# Power.net
KiCad netlist of a schematic drawn in Altium Designer
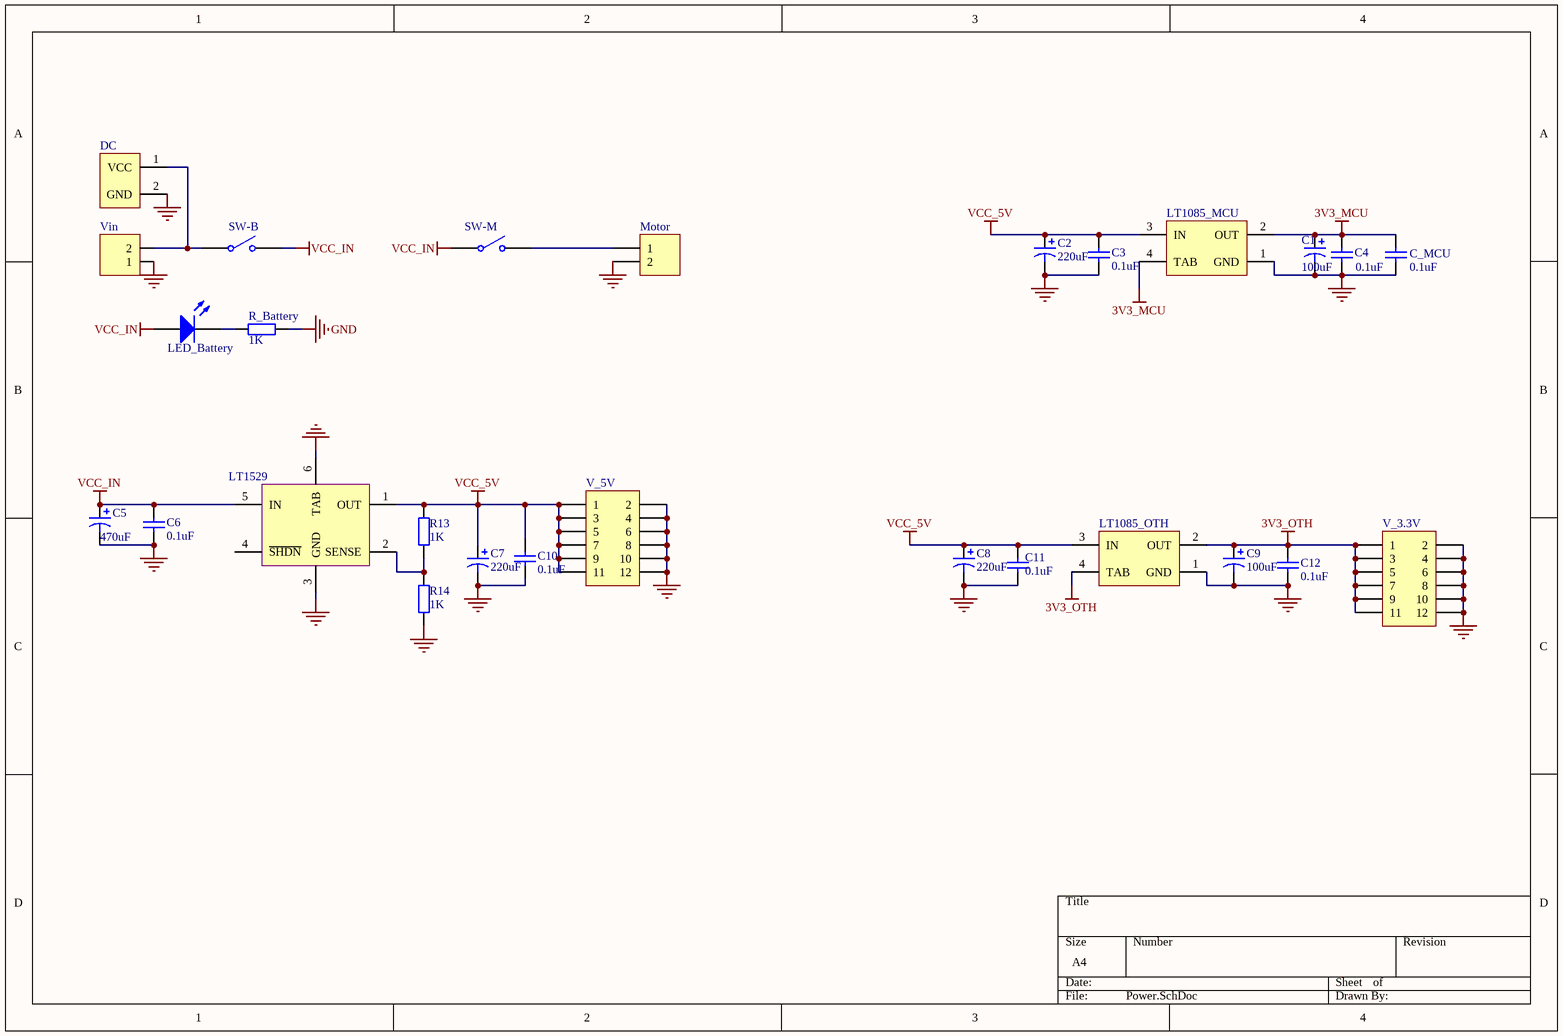
[diagram p0: Power.SchDoc]

(export (version "E")
  (design (tool "Eeschema 10.0.6"))
  (components
    (comp (ref "C1")
      (value "100uF")
      (footprint "100uf-25V")
      (description "Polarized Capacitor (Radial)")
      (fields (field (name "Comment") "100uf") (field (name "PUBLISHER") "Altium Limited"))
      (libsource (lib "Miscellaneous Devices") (part "Cap Pol1"))
    )
    (comp (ref "C2")
      (value "220uF")
      (footprint "220UF-25V")
      (description "Polarized Capacitor (Radial)")
      (fields (field (name "Comment") "220uf") (field (name "PUBLISHER") "Altium Limited"))
      (libsource (lib "Miscellaneous Devices") (part "Cap Pol1"))
    )
    (comp (ref "C3")
      (value "0.1uF")
      (footprint "0805-S")
      (description "Capacitor")
      (fields (field (name "Comment") "0.1uf") (field (name "PUBLISHER") "Altium Limited"))
      (libsource (lib "Miscellaneous Devices") (part "Cap"))
    )
    (comp (ref "C4")
      (value "0.1uF")
      (footprint "0805-S")
      (description "Capacitor")
      (fields (field (name "Comment") "0.1uf") (field (name "PUBLISHER") "Altium Limited"))
      (libsource (lib "Miscellaneous Devices") (part "Cap"))
    )
    (comp (ref "C5")
      (value "470uF")
      (footprint "220UF-25V")
      (description "Polarized Capacitor (Radial)")
      (fields (field (name "Comment") "470uf") (field (name "PUBLISHER") "Altium Limited"))
      (libsource (lib "Miscellaneous Devices") (part "Cap Pol1"))
    )
    (comp (ref "C6")
      (value "0.1uF")
      (footprint "0805-S")
      (description "Capacitor")
      (fields (field (name "PUBLISHER") "Altium Limited"))
      (libsource (lib "lichao_Library") (part "Cap_1"))
    )
    (comp (ref "C7")
      (value "220uF")
      (footprint "220UF-25V")
      (description "Polarized Capacitor (Radial)")
      (fields (field (name "Comment") "220uf") (field (name "PUBLISHER") "Altium Limited"))
      (libsource (lib "Miscellaneous Devices") (part "Cap Pol1"))
    )
    (comp (ref "C8")
      (value "220uF")
      (footprint "220UF-25V")
      (description "Polarized Capacitor (Radial)")
      (fields (field (name "Comment") "220uf") (field (name "PUBLISHER") "Altium Limited"))
      (libsource (lib "Miscellaneous Devices") (part "Cap Pol1"))
    )
    (comp (ref "C9")
      (value "100uF")
      (footprint "100uf-25V")
      (description "Polarized Capacitor (Radial)")
      (fields (field (name "Comment") "100uf") (field (name "PUBLISHER") "Altium Limited"))
      (libsource (lib "Miscellaneous Devices") (part "Cap Pol1"))
    )
    (comp (ref "C10")
      (value "0.1uF")
      (footprint "0805-S")
      (description "Capacitor")
      (fields (field (name "PUBLISHER") "Altium Limited"))
      (libsource (lib "lichao_Library") (part "Cap_1"))
    )
    (comp (ref "C11")
      (value "0.1uF")
      (footprint "0805-S")
      (description "Capacitor")
      (fields (field (name "Comment") "0.1uf") (field (name "PUBLISHER") "Altium Limited"))
      (libsource (lib "Miscellaneous Devices") (part "Cap"))
    )
    (comp (ref "C12")
      (value "0.1uF")
      (footprint "0805-S")
      (description "Capacitor")
      (fields (field (name "Comment") "0.1uf") (field (name "PUBLISHER") "Altium Limited"))
      (libsource (lib "Miscellaneous Devices") (part "Cap"))
    )
    (comp (ref "C_MCU")
      (value "0.1uF")
      (footprint "0805-S")
      (description "Capacitor")
      (fields (field (name "Comment") "0.1uf") (field (name "PUBLISHER") "Altium Limited"))
      (libsource (lib "Miscellaneous Devices") (part "Cap"))
    )
    (comp (ref "DC") (value "DC0005") (footprint "DC") (libsource (lib "lichao_Library") (part "DC0005")))
    (comp (ref "LED_Battery")
      (value "LED")
      (footprint "0805-S")
      (description "Typical INFRARED GaAs LED")
      (fields (field (name "PUBLISHER") "Altium Limited"))
      (libsource (lib "Miscellaneous Devices") (part "LED0"))
    )
    (comp (ref "LT1085_MCU")
      (value "LT1085-3.3")
      (footprint "TS3B_N")
      (libsource (lib "lichao_Library") (part "LT1085-3.3"))
    )
    (comp (ref "LT1085_OTH")
      (value "LT1085-3.3")
      (footprint "TS3B_N")
      (libsource (lib "lichao_Library") (part "LT1085-3.3"))
    )
    (comp (ref "LT1529")
      (value "LT1529")
      (footprint "TS5B")
      (libsource (lib "lichao_Library") (part "LT1529"))
    )
    (comp (ref "Motor")
      (value "Header 2")
      (footprint "Head2_small")
      (description "Header, 2-Pin")
      (fields (field (name "PUBLISHER") "Altium Limited"))
      (libsource (lib "") (part "Header 2_1"))
    )
    (comp (ref "R13")
      (value "1K")
      (footprint "0805-S")
      (description "Resistor")
      (fields (field (name "PUBLISHER") "Altium Limited"))
      (libsource (lib "lichao_Library") (part "Res2_3"))
    )
    (comp (ref "R14")
      (value "1K")
      (footprint "0805-S")
      (description "Resistor")
      (fields (field (name "PUBLISHER") "Altium Limited"))
      (libsource (lib "lichao_Library") (part "Res2_3"))
    )
    (comp (ref "R_Battery")
      (value "1K")
      (footprint "0805-S")
      (description "Resistor")
      (fields (field (name "PUBLISHER") "Altium Limited"))
      (libsource (lib "Miscellaneous Devices") (part "Res2"))
    )
    (comp (ref "SW-B")
      (value "SW-TOGGLE")
      (footprint "SW-TOGGLE")
      (description "Single-Pole, Single-Throw Switch")
      (fields (field (name "PUBLISHER") "Altium Limited"))
      (libsource (lib "lichao_Library") (part "SW-TOGGLE"))
    )
    (comp (ref "SW-M")
      (value "SW-TOGGLE")
      (footprint "SW-TOGGLE")
      (description "Single-Pole, Single-Throw Switch")
      (fields (field (name "PUBLISHER") "Altium Limited"))
      (libsource (lib "lichao_Library") (part "SW-TOGGLE"))
    )
    (comp (ref "Vin")
      (value "Header 2")
      (footprint "Head2_small")
      (description "Header, 2-Pin")
      (fields (field (name "PUBLISHER") "Altium Limited"))
      (libsource (lib "Miscellaneous Connectors") (part "Header 2"))
    )
    (comp (ref "V_3.3V")
      (value "Header 6X2")
      (footprint "HDR2X6")
      (description "Header, 6-Pin, Dual row")
      (fields (field (name "PUBLISHER") "Altium Limited"))
      (libsource (lib "Miscellaneous Connectors") (part "Header 6X2"))
    )
    (comp (ref "V_5V")
      (value "Header 6X2")
      (footprint "HDR2X6")
      (description "Header, 6-Pin, Dual row")
      (fields (field (name "PUBLISHER") "Altium Limited"))
      (libsource (lib "Miscellaneous Connectors") (part "Header 6X2"))
    )
  )
  (nets
    (net (code "1") (name "3V3_MCU") (class "Default")
      (node (ref "C1") (pin "1") (pinfunction "1_1") (pintype "passive"))
      (node (ref "C4") (pin "2") (pinfunction "2_2") (pintype "passive"))
      (node (ref "C_MCU") (pin "2") (pinfunction "2_2") (pintype "passive"))
      (node (ref "LT1085_MCU") (pin "2") (pinfunction "OUT_2") (pintype "power_in"))
      (node (ref "LT1085_MCU") (pin "4") (pinfunction "TAB_4") (pintype "power_in"))
    )
    (net (code "2") (name "3V3_OTH") (class "Default")
      (node (ref "C12") (pin "2") (pinfunction "2_2") (pintype "passive"))
      (node (ref "C9") (pin "1") (pinfunction "1_1") (pintype "passive"))
      (node (ref "LT1085_OTH") (pin "2") (pinfunction "OUT_2") (pintype "power_in"))
      (node (ref "LT1085_OTH") (pin "4") (pinfunction "TAB_4") (pintype "power_in"))
      (node (ref "V_3.3V") (pin "1") (pinfunction "1_1") (pintype "passive"))
      (node (ref "V_3.3V") (pin "11") (pinfunction "11_11") (pintype "passive"))
      (node (ref "V_3.3V") (pin "3") (pinfunction "3_3") (pintype "passive"))
      (node (ref "V_3.3V") (pin "5") (pinfunction "5_5") (pintype "passive"))
      (node (ref "V_3.3V") (pin "7") (pinfunction "7_7") (pintype "passive"))
      (node (ref "V_3.3V") (pin "9") (pinfunction "9_9") (pintype "passive"))
    )
    (net (code "3") (name "GND") (class "Default")
      (node (ref "C1") (pin "2") (pinfunction "2_2") (pintype "passive"))
      (node (ref "C10") (pin "1") (pinfunction "1_1") (pintype "passive"))
      (node (ref "C11") (pin "1") (pinfunction "1_1") (pintype "passive"))
      (node (ref "C12") (pin "1") (pinfunction "1_1") (pintype "passive"))
      (node (ref "C2") (pin "2") (pinfunction "2_2") (pintype "passive"))
      (node (ref "C3") (pin "1") (pinfunction "1_1") (pintype "passive"))
      (node (ref "C4") (pin "1") (pinfunction "1_1") (pintype "passive"))
      (node (ref "C5") (pin "2") (pinfunction "2_2") (pintype "passive"))
      (node (ref "C6") (pin "1") (pinfunction "1_1") (pintype "passive"))
      (node (ref "C7") (pin "2") (pinfunction "2_2") (pintype "passive"))
      (node (ref "C8") (pin "2") (pinfunction "2_2") (pintype "passive"))
      (node (ref "C9") (pin "2") (pinfunction "2_2") (pintype "passive"))
      (node (ref "C_MCU") (pin "1") (pinfunction "1_1") (pintype "passive"))
      (node (ref "DC") (pin "2") (pinfunction "GND_2") (pintype "open_collector"))
      (node (ref "LT1085_MCU") (pin "1") (pinfunction "GND_1") (pintype "power_in"))
      (node (ref "LT1085_OTH") (pin "1") (pinfunction "GND_1") (pintype "power_in"))
      (node (ref "LT1529") (pin "3") (pinfunction "GND_3") (pintype "passive"))
      (node (ref "LT1529") (pin "6") (pinfunction "TAB_6") (pintype "open_collector"))
      (node (ref "Motor") (pin "2") (pinfunction "2_2") (pintype "passive"))
      (node (ref "R14") (pin "1") (pinfunction "1_1") (pintype "passive"))
      (node (ref "R_Battery") (pin "1") (pinfunction "1_1") (pintype "passive"))
      (node (ref "V_3.3V") (pin "10") (pinfunction "10_10") (pintype "passive"))
      (node (ref "V_3.3V") (pin "12") (pinfunction "12_12") (pintype "passive"))
      (node (ref "V_3.3V") (pin "2") (pinfunction "2_2") (pintype "passive"))
      (node (ref "V_3.3V") (pin "4") (pinfunction "4_4") (pintype "passive"))
      (node (ref "V_3.3V") (pin "6") (pinfunction "6_6") (pintype "passive"))
      (node (ref "V_3.3V") (pin "8") (pinfunction "8_8") (pintype "passive"))
      (node (ref "V_5V") (pin "10") (pinfunction "10_10") (pintype "passive"))
      (node (ref "V_5V") (pin "12") (pinfunction "12_12") (pintype "passive"))
      (node (ref "V_5V") (pin "2") (pinfunction "2_2") (pintype "passive"))
      (node (ref "V_5V") (pin "4") (pinfunction "4_4") (pintype "passive"))
      (node (ref "V_5V") (pin "6") (pinfunction "6_6") (pintype "passive"))
      (node (ref "V_5V") (pin "8") (pinfunction "8_8") (pintype "passive"))
      (node (ref "Vin") (pin "1") (pinfunction "1_1") (pintype "passive"))
    )
    (net (code "4") (name "Net-(DC-VCC)") (class "Default")
      (node (ref "DC") (pin "1") (pinfunction "VCC_1") (pintype "open_collector"))
      (node (ref "SW-B") (pin "1") (pinfunction "COMMON_1") (pintype "passive"))
      (node (ref "Vin") (pin "2") (pinfunction "2_2") (pintype "passive"))
    )
    (net (code "5") (name "Net-(LED_Battery-K)") (class "Default")
      (node (ref "LED_Battery") (pin "2") (pinfunction "K_2") (pintype "passive"))
      (node (ref "R_Battery") (pin "2") (pinfunction "2_2") (pintype "passive"))
    )
    (net (code "6") (name "Net-(LT1529-SENSE)") (class "Default")
      (node (ref "LT1529") (pin "2") (pinfunction "SENSE_2") (pintype "passive"))
      (node (ref "R13") (pin "1") (pinfunction "1_1") (pintype "passive"))
      (node (ref "R14") (pin "2") (pinfunction "2_2") (pintype "passive"))
    )
    (net (code "7") (name "Net-(SW-M-NO)") (class "Default")
      (node (ref "Motor") (pin "1") (pinfunction "1_1") (pintype "passive"))
      (node (ref "SW-M") (pin "2") (pinfunction "NO_2") (pintype "passive"))
    )
    (net (code "8") (name "VCC_5V") (class "Default")
      (node (ref "C10") (pin "2") (pinfunction "2_2") (pintype "passive"))
      (node (ref "C11") (pin "2") (pinfunction "2_2") (pintype "passive"))
      (node (ref "C2") (pin "1") (pinfunction "1_1") (pintype "passive"))
      (node (ref "C3") (pin "2") (pinfunction "2_2") (pintype "passive"))
      (node (ref "C7") (pin "1") (pinfunction "1_1") (pintype "passive"))
      (node (ref "C8") (pin "1") (pinfunction "1_1") (pintype "passive"))
      (node (ref "LT1085_MCU") (pin "3") (pinfunction "IN_3") (pintype "power_in"))
      (node (ref "LT1085_OTH") (pin "3") (pinfunction "IN_3") (pintype "power_in"))
      (node (ref "LT1529") (pin "1") (pinfunction "OUT_1") (pintype "passive"))
      (node (ref "R13") (pin "2") (pinfunction "2_2") (pintype "passive"))
      (node (ref "V_5V") (pin "1") (pinfunction "1_1") (pintype "passive"))
      (node (ref "V_5V") (pin "11") (pinfunction "11_11") (pintype "passive"))
      (node (ref "V_5V") (pin "3") (pinfunction "3_3") (pintype "passive"))
      (node (ref "V_5V") (pin "5") (pinfunction "5_5") (pintype "passive"))
      (node (ref "V_5V") (pin "7") (pinfunction "7_7") (pintype "passive"))
      (node (ref "V_5V") (pin "9") (pinfunction "9_9") (pintype "passive"))
    )
    (net (code "9") (name "VCC_IN") (class "Default")
      (node (ref "C5") (pin "1") (pinfunction "1_1") (pintype "passive"))
      (node (ref "C6") (pin "2") (pinfunction "2_2") (pintype "passive"))
      (node (ref "LED_Battery") (pin "1") (pinfunction "A_1") (pintype "passive"))
      (node (ref "LT1529") (pin "5") (pinfunction "IN_5") (pintype "passive"))
      (node (ref "SW-B") (pin "2") (pinfunction "NO_2") (pintype "passive"))
      (node (ref "SW-M") (pin "1") (pinfunction "COMMON_1") (pintype "passive"))
    )
    (net (code "10") (name "unconnected-(LT1529-~{SHDN}-Pad4)") (class "Default")
      (node (ref "LT1529") (pin "4") (pinfunction "~{SHDN}_4") (pintype "passive"))
    )
  )
)
